# stiquito.net
KiCad netlist of a schematic drawn in EAGLE
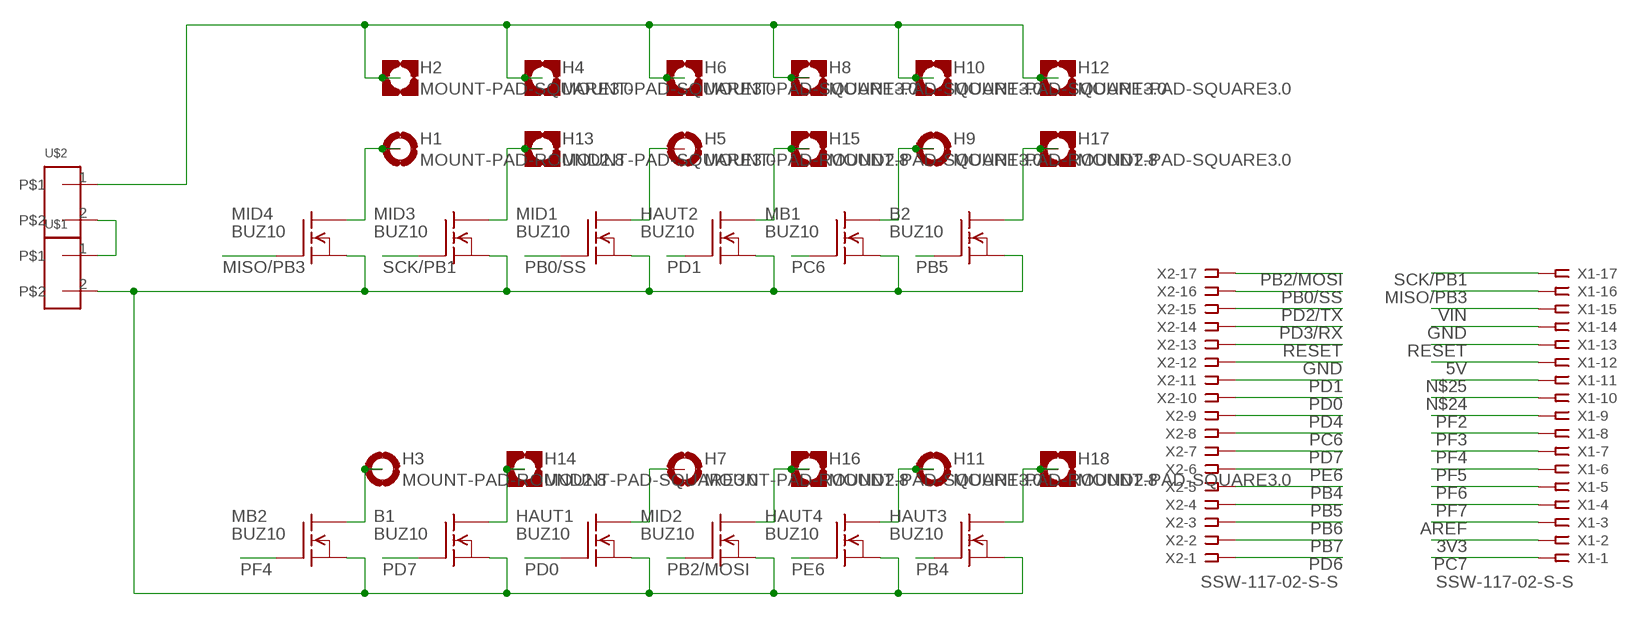
[diagram p0: schematic, sheet 1]

(export (version "E")
  (design (tool "Eeschema 10.0.6"))
  (components
    (comp (ref "B1")
      (value "BUZ10")
      (footprint "eagle-import:TO220")
      (libsource (lib "eagle-import") (part "BUZ10"))
    )
    (comp (ref "B2")
      (value "BUZ10")
      (footprint "eagle-import:TO220")
      (libsource (lib "eagle-import") (part "BUZ10"))
    )
    (comp (ref "H1")
      (value "MOUNT-PAD-ROUND2.8")
      (footprint "eagle-import:2,8-PAD")
      (libsource (lib "eagle-import") (part "MOUNT-PAD-ROUND2.8"))
    )
    (comp (ref "H2")
      (value "MOUNT-PAD-SQUARE3.0")
      (footprint "eagle-import:3,0-PAD-SQUARE")
      (libsource (lib "eagle-import") (part "MOUNT-PAD-SQUARE3.0"))
    )
    (comp (ref "H3")
      (value "MOUNT-PAD-ROUND2.8")
      (footprint "eagle-import:2,8-PAD")
      (libsource (lib "eagle-import") (part "MOUNT-PAD-ROUND2.8"))
    )
    (comp (ref "H4")
      (value "MOUNT-PAD-SQUARE3.0")
      (footprint "eagle-import:3,0-PAD-SQUARE")
      (libsource (lib "eagle-import") (part "MOUNT-PAD-SQUARE3.0"))
    )
    (comp (ref "H5")
      (value "MOUNT-PAD-ROUND2.8")
      (footprint "eagle-import:2,8-PAD")
      (libsource (lib "eagle-import") (part "MOUNT-PAD-ROUND2.8"))
    )
    (comp (ref "H6")
      (value "MOUNT-PAD-SQUARE3.0")
      (footprint "eagle-import:3,0-PAD-SQUARE")
      (libsource (lib "eagle-import") (part "MOUNT-PAD-SQUARE3.0"))
    )
    (comp (ref "H7")
      (value "MOUNT-PAD-ROUND2.8")
      (footprint "eagle-import:2,8-PAD")
      (libsource (lib "eagle-import") (part "MOUNT-PAD-ROUND2.8"))
    )
    (comp (ref "H8")
      (value "MOUNT-PAD-SQUARE3.0")
      (footprint "eagle-import:3,0-PAD-SQUARE")
      (libsource (lib "eagle-import") (part "MOUNT-PAD-SQUARE3.0"))
    )
    (comp (ref "H9")
      (value "MOUNT-PAD-ROUND2.8")
      (footprint "eagle-import:2,8-PAD")
      (libsource (lib "eagle-import") (part "MOUNT-PAD-ROUND2.8"))
    )
    (comp (ref "H10")
      (value "MOUNT-PAD-SQUARE3.0")
      (footprint "eagle-import:3,0-PAD-SQUARE")
      (libsource (lib "eagle-import") (part "MOUNT-PAD-SQUARE3.0"))
    )
    (comp (ref "H11")
      (value "MOUNT-PAD-ROUND2.8")
      (footprint "eagle-import:2,8-PAD")
      (libsource (lib "eagle-import") (part "MOUNT-PAD-ROUND2.8"))
    )
    (comp (ref "H12")
      (value "MOUNT-PAD-SQUARE3.0")
      (footprint "eagle-import:3,0-PAD-SQUARE")
      (libsource (lib "eagle-import") (part "MOUNT-PAD-SQUARE3.0"))
    )
    (comp (ref "H13")
      (value "MOUNT-PAD-SQUARE3.0")
      (footprint "eagle-import:3,0-PAD-SQUARE")
      (libsource (lib "eagle-import") (part "MOUNT-PAD-SQUARE3.0"))
    )
    (comp (ref "H14")
      (value "MOUNT-PAD-SQUARE3.0")
      (footprint "eagle-import:3,0-PAD-SQUARE")
      (libsource (lib "eagle-import") (part "MOUNT-PAD-SQUARE3.0"))
    )
    (comp (ref "H15")
      (value "MOUNT-PAD-SQUARE3.0")
      (footprint "eagle-import:3,0-PAD-SQUARE")
      (libsource (lib "eagle-import") (part "MOUNT-PAD-SQUARE3.0"))
    )
    (comp (ref "H16")
      (value "MOUNT-PAD-SQUARE3.0")
      (footprint "eagle-import:3,0-PAD-SQUARE")
      (libsource (lib "eagle-import") (part "MOUNT-PAD-SQUARE3.0"))
    )
    (comp (ref "H17")
      (value "MOUNT-PAD-SQUARE3.0")
      (footprint "eagle-import:3,0-PAD-SQUARE")
      (libsource (lib "eagle-import") (part "MOUNT-PAD-SQUARE3.0"))
    )
    (comp (ref "H18")
      (value "MOUNT-PAD-SQUARE3.0")
      (footprint "eagle-import:3,0-PAD-SQUARE")
      (libsource (lib "eagle-import") (part "MOUNT-PAD-SQUARE3.0"))
    )
    (comp (ref "HAUT1")
      (value "BUZ10")
      (footprint "eagle-import:TO220")
      (libsource (lib "eagle-import") (part "BUZ10"))
    )
    (comp (ref "HAUT2")
      (value "BUZ10")
      (footprint "eagle-import:TO220")
      (libsource (lib "eagle-import") (part "BUZ10"))
    )
    (comp (ref "HAUT3")
      (value "BUZ10")
      (footprint "eagle-import:TO220")
      (libsource (lib "eagle-import") (part "BUZ10"))
    )
    (comp (ref "HAUT4")
      (value "BUZ10")
      (footprint "eagle-import:TO220")
      (libsource (lib "eagle-import") (part "BUZ10"))
    )
    (comp (ref "MB1")
      (value "BUZ10")
      (footprint "eagle-import:TO220")
      (libsource (lib "eagle-import") (part "BUZ10"))
    )
    (comp (ref "MB2")
      (value "BUZ10")
      (footprint "eagle-import:TO220")
      (libsource (lib "eagle-import") (part "BUZ10"))
    )
    (comp (ref "MID1")
      (value "BUZ10")
      (footprint "eagle-import:TO220")
      (libsource (lib "eagle-import") (part "BUZ10"))
    )
    (comp (ref "MID2")
      (value "BUZ10")
      (footprint "eagle-import:TO220")
      (libsource (lib "eagle-import") (part "BUZ10"))
    )
    (comp (ref "MID3")
      (value "BUZ10")
      (footprint "eagle-import:TO220")
      (libsource (lib "eagle-import") (part "BUZ10"))
    )
    (comp (ref "MID4")
      (value "BUZ10")
      (footprint "eagle-import:TO220")
      (libsource (lib "eagle-import") (part "BUZ10"))
    )
    (comp (ref "U$1")
      (value "MOLEX_KK_2")
      (footprint "eagle-import:MOLEX_KK_2")
      (libsource (lib "eagle-import") (part "MOLEX_KK_2"))
    )
    (comp (ref "U$2")
      (value "MOLEX_KK_2")
      (footprint "eagle-import:MOLEX_KK_2")
      (libsource (lib "eagle-import") (part "MOLEX_KK_2"))
    )
    (comp (ref "X1")
      (value "SSW-117-02-S-S")
      (footprint "eagle-import:SSW-117-02-S-S")
      (libsource (lib "eagle-import") (part "SSW-117-02-S-S"))
    )
    (comp (ref "X2")
      (value "SSW-117-02-S-S")
      (footprint "eagle-import:SSW-117-02-S-S")
      (libsource (lib "eagle-import") (part "SSW-117-02-S-S"))
    )
  )
  (nets
    (net (code "1") (name "/3V3") (class "Default")
      (node (ref "X1") (pin "2") (pinfunction "1_2") (pintype "passive"))
    )
    (net (code "2") (name "/5V") (class "Default")
      (node (ref "X1") (pin "12") (pinfunction "1_12") (pintype "passive"))
    )
    (net (code "3") (name "/AREF") (class "Default")
      (node (ref "X1") (pin "3") (pinfunction "1_3") (pintype "passive"))
    )
    (net (code "4") (name "/GND") (class "Default")
      (node (ref "B1") (pin "3") (pinfunction "S_3") (pintype "passive"))
      (node (ref "B2") (pin "3") (pinfunction "S_3") (pintype "passive"))
      (node (ref "HAUT1") (pin "3") (pinfunction "S_3") (pintype "passive"))
      (node (ref "HAUT2") (pin "3") (pinfunction "S_3") (pintype "passive"))
      (node (ref "HAUT3") (pin "3") (pinfunction "S_3") (pintype "passive"))
      (node (ref "HAUT4") (pin "3") (pinfunction "S_3") (pintype "passive"))
      (node (ref "MB1") (pin "3") (pinfunction "S_3") (pintype "passive"))
      (node (ref "MB2") (pin "3") (pinfunction "S_3") (pintype "passive"))
      (node (ref "MID1") (pin "3") (pinfunction "S_3") (pintype "passive"))
      (node (ref "MID2") (pin "3") (pinfunction "S_3") (pintype "passive"))
      (node (ref "MID3") (pin "3") (pinfunction "S_3") (pintype "passive"))
      (node (ref "MID4") (pin "3") (pinfunction "S_3") (pintype "passive"))
      (node (ref "U$1") (pin "2") (pinfunction "P$2_2") (pintype "bidirectional"))
      (node (ref "X1") (pin "14") (pinfunction "1_14") (pintype "passive"))
      (node (ref "X2") (pin "12") (pinfunction "1_12") (pintype "passive"))
    )
    (net (code "5") (name "/MISO{slash}PB3") (class "Default")
      (node (ref "MID4") (pin "1") (pinfunction "G_1") (pintype "passive"))
      (node (ref "X1") (pin "16") (pinfunction "1_16") (pintype "passive"))
    )
    (net (code "6") (name "/N$24") (class "Default")
      (node (ref "X1") (pin "10") (pinfunction "1_10") (pintype "passive"))
    )
    (net (code "7") (name "/N$25") (class "Default")
      (node (ref "X1") (pin "11") (pinfunction "1_11") (pintype "passive"))
    )
    (net (code "8") (name "/PB0{slash}SS") (class "Default")
      (node (ref "MID1") (pin "1") (pinfunction "G_1") (pintype "passive"))
      (node (ref "X2") (pin "16") (pinfunction "1_16") (pintype "passive"))
    )
    (net (code "9") (name "/PB2{slash}MOSI") (class "Default")
      (node (ref "MID2") (pin "1") (pinfunction "G_1") (pintype "passive"))
      (node (ref "X2") (pin "17") (pinfunction "1_17") (pintype "passive"))
    )
    (net (code "10") (name "/PB4") (class "Default")
      (node (ref "HAUT3") (pin "1") (pinfunction "G_1") (pintype "passive"))
      (node (ref "X2") (pin "5") (pinfunction "1_5") (pintype "passive"))
    )
    (net (code "11") (name "/PB5") (class "Default")
      (node (ref "B2") (pin "1") (pinfunction "G_1") (pintype "passive"))
      (node (ref "X2") (pin "4") (pinfunction "1_4") (pintype "passive"))
    )
    (net (code "12") (name "/PB6") (class "Default")
      (node (ref "X2") (pin "3") (pinfunction "1_3") (pintype "passive"))
    )
    (net (code "13") (name "/PB7") (class "Default")
      (node (ref "X2") (pin "2") (pinfunction "1_2") (pintype "passive"))
    )
    (net (code "14") (name "/PC6") (class "Default")
      (node (ref "MB1") (pin "1") (pinfunction "G_1") (pintype "passive"))
      (node (ref "X2") (pin "8") (pinfunction "1_8") (pintype "passive"))
    )
    (net (code "15") (name "/PC7") (class "Default")
      (node (ref "X1") (pin "1") (pinfunction "1_1") (pintype "passive"))
    )
    (net (code "16") (name "/PD0") (class "Default")
      (node (ref "HAUT1") (pin "1") (pinfunction "G_1") (pintype "passive"))
      (node (ref "X2") (pin "10") (pinfunction "1_10") (pintype "passive"))
    )
    (net (code "17") (name "/PD1") (class "Default")
      (node (ref "HAUT2") (pin "1") (pinfunction "G_1") (pintype "passive"))
      (node (ref "X2") (pin "11") (pinfunction "1_11") (pintype "passive"))
    )
    (net (code "18") (name "/PD2{slash}TX") (class "Default")
      (node (ref "X2") (pin "15") (pinfunction "1_15") (pintype "passive"))
    )
    (net (code "19") (name "/PD3{slash}RX") (class "Default")
      (node (ref "X2") (pin "14") (pinfunction "1_14") (pintype "passive"))
    )
    (net (code "20") (name "/PD4") (class "Default")
      (node (ref "X2") (pin "9") (pinfunction "1_9") (pintype "passive"))
    )
    (net (code "21") (name "/PD6") (class "Default")
      (node (ref "X2") (pin "1") (pinfunction "1_1") (pintype "passive"))
    )
    (net (code "22") (name "/PD7") (class "Default")
      (node (ref "B1") (pin "1") (pinfunction "G_1") (pintype "passive"))
      (node (ref "X2") (pin "7") (pinfunction "1_7") (pintype "passive"))
    )
    (net (code "23") (name "/PE6") (class "Default")
      (node (ref "HAUT4") (pin "1") (pinfunction "G_1") (pintype "passive"))
      (node (ref "X2") (pin "6") (pinfunction "1_6") (pintype "passive"))
    )
    (net (code "24") (name "/PF2") (class "Default")
      (node (ref "X1") (pin "9") (pinfunction "1_9") (pintype "passive"))
    )
    (net (code "25") (name "/PF3") (class "Default")
      (node (ref "X1") (pin "8") (pinfunction "1_8") (pintype "passive"))
    )
    (net (code "26") (name "/PF4") (class "Default")
      (node (ref "MB2") (pin "1") (pinfunction "G_1") (pintype "passive"))
      (node (ref "X1") (pin "7") (pinfunction "1_7") (pintype "passive"))
    )
    (net (code "27") (name "/PF5") (class "Default")
      (node (ref "X1") (pin "6") (pinfunction "1_6") (pintype "passive"))
    )
    (net (code "28") (name "/PF6") (class "Default")
      (node (ref "X1") (pin "5") (pinfunction "1_5") (pintype "passive"))
    )
    (net (code "29") (name "/PF7") (class "Default")
      (node (ref "X1") (pin "4") (pinfunction "1_4") (pintype "passive"))
    )
    (net (code "30") (name "/RESET") (class "Default")
      (node (ref "X1") (pin "13") (pinfunction "1_13") (pintype "passive"))
      (node (ref "X2") (pin "13") (pinfunction "1_13") (pintype "passive"))
    )
    (net (code "31") (name "/SCK{slash}PB1") (class "Default")
      (node (ref "MID3") (pin "1") (pinfunction "G_1") (pintype "passive"))
      (node (ref "X1") (pin "17") (pinfunction "1_17") (pintype "passive"))
    )
    (net (code "32") (name "/VIN") (class "Default")
      (node (ref "H10") (pin "B3,0") (pinfunction "MOUNT_B3,0") (pintype "passive"))
      (node (ref "H12") (pin "B3,0") (pinfunction "MOUNT_B3,0") (pintype "passive"))
      (node (ref "H2") (pin "B3,0") (pinfunction "MOUNT_B3,0") (pintype "passive"))
      (node (ref "H4") (pin "B3,0") (pinfunction "MOUNT_B3,0") (pintype "passive"))
      (node (ref "H6") (pin "B3,0") (pinfunction "MOUNT_B3,0") (pintype "passive"))
      (node (ref "H8") (pin "B3,0") (pinfunction "MOUNT_B3,0") (pintype "passive"))
      (node (ref "U$2") (pin "1") (pinfunction "P$1_1") (pintype "bidirectional"))
      (node (ref "X1") (pin "15") (pinfunction "1_15") (pintype "passive"))
    )
    (net (code "33") (name "Net-(B1-D)") (class "Default")
      (node (ref "B1") (pin "2") (pinfunction "D_2") (pintype "passive"))
      (node (ref "H14") (pin "B3,0") (pinfunction "MOUNT_B3,0") (pintype "passive"))
    )
    (net (code "34") (name "Net-(B2-D)") (class "Default")
      (node (ref "B2") (pin "2") (pinfunction "D_2") (pintype "passive"))
      (node (ref "H17") (pin "B3,0") (pinfunction "MOUNT_B3,0") (pintype "passive"))
    )
    (net (code "35") (name "Net-(H1-MOUNT)") (class "Default")
      (node (ref "H1") (pin "B2,8") (pinfunction "MOUNT_B2,8") (pintype "passive"))
      (node (ref "MID4") (pin "2") (pinfunction "D_2") (pintype "passive"))
    )
    (net (code "36") (name "Net-(H3-MOUNT)") (class "Default")
      (node (ref "H3") (pin "B2,8") (pinfunction "MOUNT_B2,8") (pintype "passive"))
      (node (ref "MB2") (pin "2") (pinfunction "D_2") (pintype "passive"))
    )
    (net (code "37") (name "Net-(H5-MOUNT)") (class "Default")
      (node (ref "H5") (pin "B2,8") (pinfunction "MOUNT_B2,8") (pintype "passive"))
      (node (ref "MID1") (pin "2") (pinfunction "D_2") (pintype "passive"))
    )
    (net (code "38") (name "Net-(H7-MOUNT)") (class "Default")
      (node (ref "H7") (pin "B2,8") (pinfunction "MOUNT_B2,8") (pintype "passive"))
      (node (ref "HAUT1") (pin "2") (pinfunction "D_2") (pintype "passive"))
    )
    (net (code "39") (name "Net-(H9-MOUNT)") (class "Default")
      (node (ref "H9") (pin "B2,8") (pinfunction "MOUNT_B2,8") (pintype "passive"))
      (node (ref "MB1") (pin "2") (pinfunction "D_2") (pintype "passive"))
    )
    (net (code "40") (name "Net-(H11-MOUNT)") (class "Default")
      (node (ref "H11") (pin "B2,8") (pinfunction "MOUNT_B2,8") (pintype "passive"))
      (node (ref "HAUT4") (pin "2") (pinfunction "D_2") (pintype "passive"))
    )
    (net (code "41") (name "Net-(H13-MOUNT)") (class "Default")
      (node (ref "H13") (pin "B3,0") (pinfunction "MOUNT_B3,0") (pintype "passive"))
      (node (ref "MID3") (pin "2") (pinfunction "D_2") (pintype "passive"))
    )
    (net (code "42") (name "Net-(H15-MOUNT)") (class "Default")
      (node (ref "H15") (pin "B3,0") (pinfunction "MOUNT_B3,0") (pintype "passive"))
      (node (ref "HAUT2") (pin "2") (pinfunction "D_2") (pintype "passive"))
    )
    (net (code "43") (name "Net-(H16-MOUNT)") (class "Default")
      (node (ref "H16") (pin "B3,0") (pinfunction "MOUNT_B3,0") (pintype "passive"))
      (node (ref "MID2") (pin "2") (pinfunction "D_2") (pintype "passive"))
    )
    (net (code "44") (name "Net-(H18-MOUNT)") (class "Default")
      (node (ref "H18") (pin "B3,0") (pinfunction "MOUNT_B3,0") (pintype "passive"))
      (node (ref "HAUT3") (pin "2") (pinfunction "D_2") (pintype "passive"))
    )
    (net (code "45") (name "Net-(U$1-P$1)") (class "Default")
      (node (ref "U$1") (pin "1") (pinfunction "P$1_1") (pintype "bidirectional"))
      (node (ref "U$2") (pin "2") (pinfunction "P$2_2") (pintype "bidirectional"))
    )
  )
)
